# Rectifier_Stage.net
KiCad netlist of a schematic drawn in Altium Designer
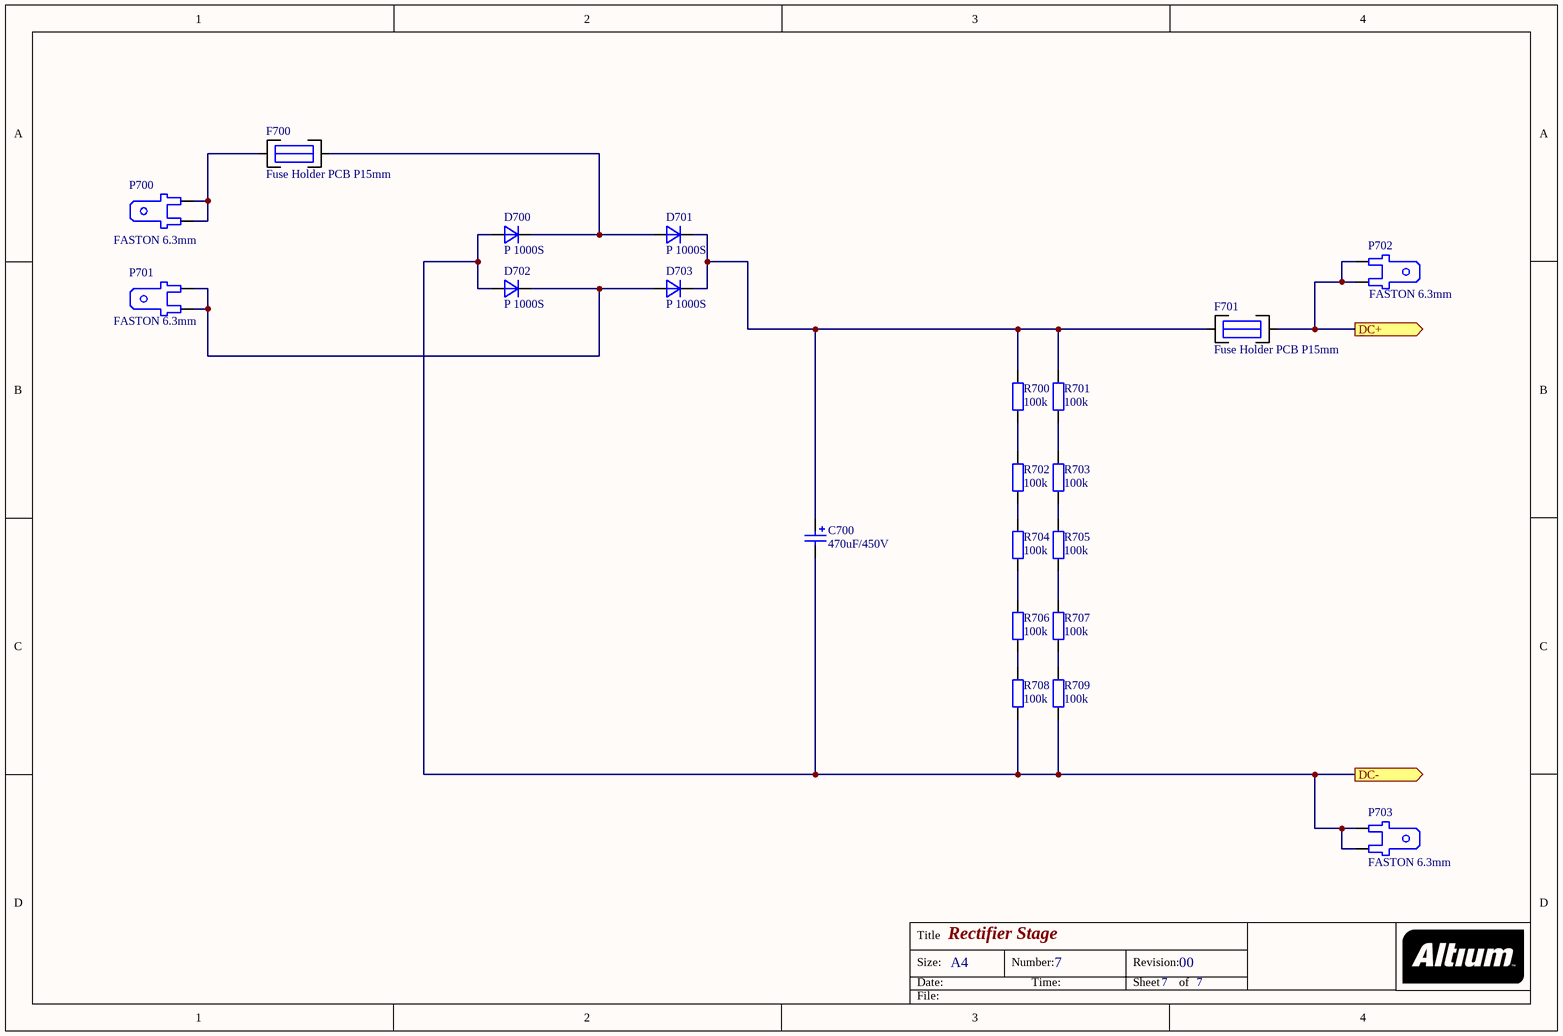
[diagram p0: Rectifier Stage.SchDoc]

(export (version "E")
  (design (tool "Eeschema 10.0.6"))
  (components
    (comp (ref "C700")
      (value "470uF/450V")
      (footprint "CAPR 52X35")
      (fields (field (name "Comment") "Cap"))
      (libsource (lib "Capacitors") (part "Cap pol"))
    )
    (comp (ref "D700")
      (value "P 1000S")
      (footprint "P 1000 S")
      (description "Standard silicon rectifier  diode")
      (libsource (lib "Diode") (part "P 1000S"))
    )
    (comp (ref "D701")
      (value "P 1000S")
      (footprint "P 1000 S")
      (description "Standard silicon rectifier  diode")
      (libsource (lib "Diode") (part "P 1000S"))
    )
    (comp (ref "D702")
      (value "P 1000S")
      (footprint "P 1000 S")
      (description "Standard silicon rectifier  diode")
      (libsource (lib "Diode") (part "P 1000S"))
    )
    (comp (ref "D703")
      (value "P 1000S")
      (footprint "P 1000 S")
      (description "Standard silicon rectifier  diode")
      (libsource (lib "Diode") (part "P 1000S"))
    )
    (comp (ref "F700")
      (value "Fuse Holder PCB P15mm")
      (footprint "Fuse Holder PCB P15mm")
      (libsource (lib "Fuse") (part "Fuse Holder PCB P15mm"))
    )
    (comp (ref "F701")
      (value "Fuse Holder PCB P15mm")
      (footprint "Fuse Holder PCB P15mm")
      (libsource (lib "Fuse") (part "Fuse Holder PCB P15mm"))
    )
    (comp (ref "P700")
      (value "FASTON 6.3mm")
      (footprint "FASTON 6.3mm")
      (fields (field (name "Comment") "FASTON 6.3MM"))
      (libsource (lib "Connector") (part "FASTON 6.3MM"))
    )
    (comp (ref "P701")
      (value "FASTON 6.3mm")
      (footprint "FASTON 6.3mm")
      (fields (field (name "Comment") "FASTON 6.3MM"))
      (libsource (lib "Connector") (part "FASTON 6.3MM"))
    )
    (comp (ref "P702")
      (value "FASTON 6.3mm")
      (footprint "FASTON 6.3mm")
      (fields (field (name "Comment") "FASTON 6.3MM"))
      (libsource (lib "Connector") (part "FASTON 6.3MM"))
    )
    (comp (ref "P703")
      (value "FASTON 6.3mm")
      (footprint "FASTON 6.3mm")
      (fields (field (name "Comment") "FASTON 6.3MM"))
      (libsource (lib "Connector") (part "FASTON 6.3MM"))
    )
    (comp (ref "R700")
      (value "100k")
      (footprint "1206_REFLOW")
      (fields (field (name "Comment") "RES"))
      (libsource (lib "Resistor") (part "RES 1"))
    )
    (comp (ref "R701")
      (value "100k")
      (footprint "1206_REFLOW")
      (fields (field (name "Comment") "RES"))
      (libsource (lib "Resistor") (part "RES 1"))
    )
    (comp (ref "R702")
      (value "100k")
      (footprint "1206_REFLOW")
      (fields (field (name "Comment") "RES"))
      (libsource (lib "Resistor") (part "RES 1"))
    )
    (comp (ref "R703")
      (value "100k")
      (footprint "1206_REFLOW")
      (fields (field (name "Comment") "RES"))
      (libsource (lib "Resistor") (part "RES 1"))
    )
    (comp (ref "R704")
      (value "100k")
      (footprint "1206_REFLOW")
      (fields (field (name "Comment") "RES"))
      (libsource (lib "Resistor") (part "RES 1"))
    )
    (comp (ref "R705")
      (value "100k")
      (footprint "1206_REFLOW")
      (fields (field (name "Comment") "RES"))
      (libsource (lib "Resistor") (part "RES 1"))
    )
    (comp (ref "R706")
      (value "100k")
      (footprint "1206_REFLOW")
      (fields (field (name "Comment") "RES"))
      (libsource (lib "Resistor") (part "RES 1"))
    )
    (comp (ref "R707")
      (value "100k")
      (footprint "1206_REFLOW")
      (fields (field (name "Comment") "RES"))
      (libsource (lib "Resistor") (part "RES 1"))
    )
    (comp (ref "R708")
      (value "100k")
      (footprint "1206_REFLOW")
      (fields (field (name "Comment") "RES"))
      (libsource (lib "Resistor") (part "RES 1"))
    )
    (comp (ref "R709")
      (value "100k")
      (footprint "1206_REFLOW")
      (fields (field (name "Comment") "RES"))
      (libsource (lib "Resistor") (part "RES 1"))
    )
  )
  (nets
    (net (code "1") (name "/DC+") (class "Default")
      (node (ref "F701") (pin "2") (pinfunction "2_2") (pintype "passive"))
      (node (ref "P702") (pin "1") (pinfunction "1_1") (pintype "passive"))
      (node (ref "P702") (pin "2") (pinfunction "2_2") (pintype "passive"))
    )
    (net (code "2") (name "/DC-") (class "Default")
      (node (ref "C700") (pin "2") (pinfunction "2_2") (pintype "passive"))
      (node (ref "D700") (pin "A") (pintype "passive"))
      (node (ref "D702") (pin "A") (pintype "passive"))
      (node (ref "P703") (pin "1") (pinfunction "1_1") (pintype "passive"))
      (node (ref "P703") (pin "2") (pinfunction "2_2") (pintype "passive"))
      (node (ref "R708") (pin "2") (pinfunction "2_2") (pintype "passive"))
      (node (ref "R709") (pin "2") (pinfunction "2_2") (pintype "passive"))
    )
    (net (code "3") (name "Net-(C700-Pad1)") (class "Default")
      (node (ref "C700") (pin "1") (pinfunction "1_1") (pintype "passive"))
      (node (ref "D701") (pin "K") (pintype "passive"))
      (node (ref "D703") (pin "K") (pintype "passive"))
      (node (ref "F701") (pin "1") (pinfunction "1_1") (pintype "passive"))
      (node (ref "R700") (pin "1") (pinfunction "1_1") (pintype "passive"))
      (node (ref "R701") (pin "1") (pinfunction "1_1") (pintype "passive"))
    )
    (net (code "4") (name "Net-(D700-PadK)") (class "Default")
      (node (ref "D700") (pin "K") (pintype "passive"))
      (node (ref "D701") (pin "A") (pintype "passive"))
      (node (ref "F700") (pin "2") (pinfunction "2_2") (pintype "passive"))
    )
    (net (code "5") (name "Net-(D702-PadK)") (class "Default")
      (node (ref "D702") (pin "K") (pintype "passive"))
      (node (ref "D703") (pin "A") (pintype "passive"))
      (node (ref "P701") (pin "1") (pinfunction "1_1") (pintype "passive"))
      (node (ref "P701") (pin "2") (pinfunction "2_2") (pintype "passive"))
    )
    (net (code "6") (name "Net-(F700-Pad1)") (class "Default")
      (node (ref "F700") (pin "1") (pinfunction "1_1") (pintype "passive"))
      (node (ref "P700") (pin "1") (pinfunction "1_1") (pintype "passive"))
      (node (ref "P700") (pin "2") (pinfunction "2_2") (pintype "passive"))
    )
    (net (code "7") (name "Net-(R700-Pad2)") (class "Default")
      (node (ref "R700") (pin "2") (pinfunction "2_2") (pintype "passive"))
      (node (ref "R702") (pin "1") (pinfunction "1_1") (pintype "passive"))
    )
    (net (code "8") (name "Net-(R701-Pad2)") (class "Default")
      (node (ref "R701") (pin "2") (pinfunction "2_2") (pintype "passive"))
      (node (ref "R703") (pin "1") (pinfunction "1_1") (pintype "passive"))
    )
    (net (code "9") (name "Net-(R702-Pad2)") (class "Default")
      (node (ref "R702") (pin "2") (pinfunction "2_2") (pintype "passive"))
      (node (ref "R704") (pin "1") (pinfunction "1_1") (pintype "passive"))
    )
    (net (code "10") (name "Net-(R703-Pad2)") (class "Default")
      (node (ref "R703") (pin "2") (pinfunction "2_2") (pintype "passive"))
      (node (ref "R705") (pin "1") (pinfunction "1_1") (pintype "passive"))
    )
    (net (code "11") (name "Net-(R704-Pad2)") (class "Default")
      (node (ref "R704") (pin "2") (pinfunction "2_2") (pintype "passive"))
      (node (ref "R706") (pin "1") (pinfunction "1_1") (pintype "passive"))
    )
    (net (code "12") (name "Net-(R705-Pad2)") (class "Default")
      (node (ref "R705") (pin "2") (pinfunction "2_2") (pintype "passive"))
      (node (ref "R707") (pin "1") (pinfunction "1_1") (pintype "passive"))
    )
    (net (code "13") (name "Net-(R706-Pad2)") (class "Default")
      (node (ref "R706") (pin "2") (pinfunction "2_2") (pintype "passive"))
      (node (ref "R708") (pin "1") (pinfunction "1_1") (pintype "passive"))
    )
    (net (code "14") (name "Net-(R707-Pad2)") (class "Default")
      (node (ref "R707") (pin "2") (pinfunction "2_2") (pintype "passive"))
      (node (ref "R709") (pin "1") (pinfunction "1_1") (pintype "passive"))
    )
  )
)
